# 3_Peripherals.net
KiCad netlist of a schematic drawn in Altium Designer
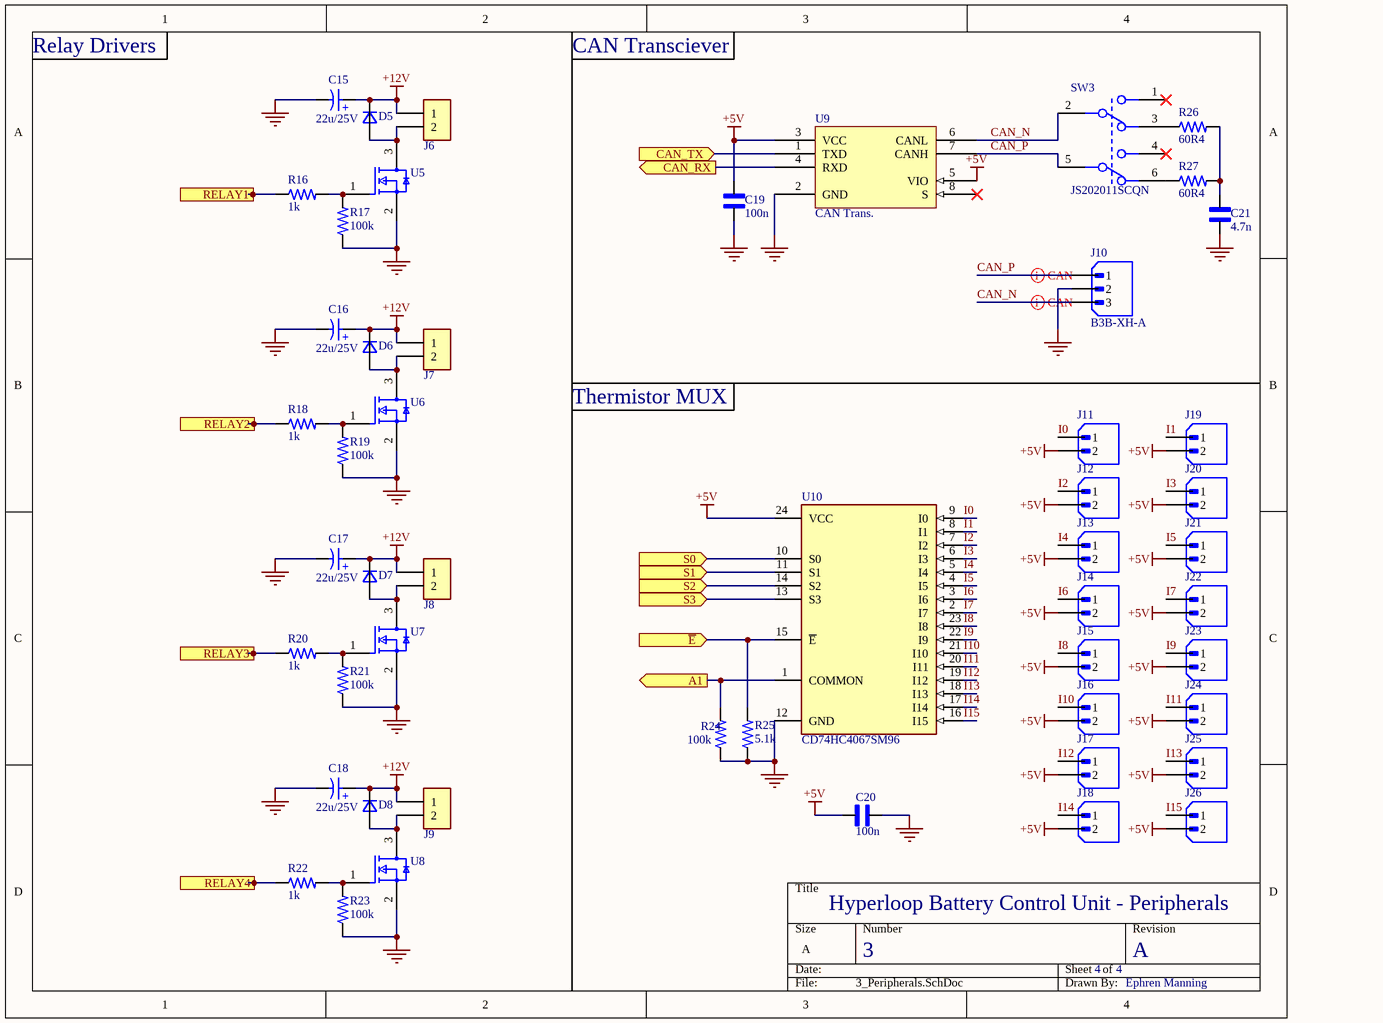
[diagram p0: 3_Peripherals.SchDoc]

(export (version "E")
  (design (tool "Eeschema 10.0.6"))
  (components
    (comp (ref "C15")
      (value "22u/25V")
      (footprint "WCAP-ASLI_D5H5.5")
      (description "22uF/25V Alum")
      (libsource (lib "SAE @ UIC Formula Electric") (part "Capacitor_Polarized"))
    )
    (comp (ref "C16")
      (value "22u/25V")
      (footprint "WCAP-ASLI_D5H5.5")
      (description "22uF/25V Alum")
      (libsource (lib "SAE @ UIC Formula Electric") (part "Capacitor_Polarized"))
    )
    (comp (ref "C17")
      (value "22u/25V")
      (footprint "WCAP-ASLI_D5H5.5")
      (description "22uF/25V Alum")
      (libsource (lib "SAE @ UIC Formula Electric") (part "Capacitor_Polarized"))
    )
    (comp (ref "C18")
      (value "22u/25V")
      (footprint "WCAP-ASLI_D5H5.5")
      (description "22uF/25V Alum")
      (libsource (lib "SAE @ UIC Formula Electric") (part "Capacitor_Polarized"))
    )
    (comp (ref "C19")
      (value "100n")
      (footprint "CAP_0603-Footprint")
      (description "100nF/16V ±10% Ceramic 0603")
      (libsource (lib "SAE @ UIC Formula Electric") (part "CAP_0603-Symbol"))
    )
    (comp (ref "C20")
      (value "100n")
      (footprint "CAP_0603-Footprint")
      (description "100nF/16V ±10% Ceramic 0603")
      (libsource (lib "") (part "CAP_0603-Symbol_1"))
    )
    (comp (ref "C21")
      (value "4.7n")
      (footprint "CAP_0603-Footprint")
      (description "4.7nF/16V 0603 Ceramic Cap")
      (libsource (lib "SAE @ UIC Formula Electric") (part "CAP_0603-Symbol"))
    )
    (comp (ref "D5")
      (value "1N4007FL")
      (footprint "SOD-123_ONS")
      (description "1000V 1A Diode")
      (libsource (lib "SAE @ UIC Formula Electric") (part "1N4007FL-Symbol"))
    )
    (comp (ref "D6")
      (value "1N4007FL")
      (footprint "SOD-123_ONS")
      (description "1000V 1A Diode")
      (libsource (lib "SAE @ UIC Formula Electric") (part "1N4007FL-Symbol"))
    )
    (comp (ref "D7")
      (value "1N4007FL")
      (footprint "SOD-123_ONS")
      (description "1000V 1A Diode")
      (libsource (lib "SAE @ UIC Formula Electric") (part "1N4007FL-Symbol"))
    )
    (comp (ref "D8")
      (value "1N4007FL")
      (footprint "SOD-123_ONS")
      (description "1000V 1A Diode")
      (libsource (lib "SAE @ UIC Formula Electric") (part "1N4007FL-Symbol"))
    )
    (comp (ref "J6")
      (value "282837-2")
      (footprint "TE_282837-2")
      (description "2x Screw Terminal")
      (libsource (lib "SAE @ UIC Formula Electric") (part "282837-2"))
    )
    (comp (ref "J7")
      (value "282837-2")
      (footprint "TE_282837-2")
      (description "2x Screw Terminal")
      (libsource (lib "SAE @ UIC Formula Electric") (part "282837-2"))
    )
    (comp (ref "J8")
      (value "282837-2")
      (footprint "TE_282837-2")
      (description "2x Screw Terminal")
      (libsource (lib "SAE @ UIC Formula Electric") (part "282837-2"))
    )
    (comp (ref "J9")
      (value "282837-2")
      (footprint "TE_282837-2")
      (description "2x Screw Terminal")
      (libsource (lib "SAE @ UIC Formula Electric") (part "282837-2"))
    )
    (comp (ref "J10")
      (value "B3B-XH-A")
      (footprint "JST_B3B-XH-A")
      (description "3x Pin JST-XH-A")
      (libsource (lib "SAE @ UIC Formula Electric") (part "B3B-XH-A"))
    )
    (comp (ref "J11")
      (value "B2B-XH-A")
      (footprint "JST_B2B-XH-A")
      (description "2x Pin JST-XH")
      (libsource (lib "SAE @ UIC Formula Electric") (part "B2B-XH-A"))
    )
    (comp (ref "J12")
      (value "B2B-XH-A")
      (footprint "JST_B2B-XH-A")
      (description "2x Pin JST-XH")
      (libsource (lib "SAE @ UIC Formula Electric") (part "B2B-XH-A"))
    )
    (comp (ref "J13")
      (value "B2B-XH-A")
      (footprint "JST_B2B-XH-A")
      (description "2x Pin JST-XH")
      (libsource (lib "SAE @ UIC Formula Electric") (part "B2B-XH-A"))
    )
    (comp (ref "J14")
      (value "B2B-XH-A")
      (footprint "JST_B2B-XH-A")
      (description "2x Pin JST-XH")
      (libsource (lib "SAE @ UIC Formula Electric") (part "B2B-XH-A"))
    )
    (comp (ref "J15")
      (value "B2B-XH-A")
      (footprint "JST_B2B-XH-A")
      (description "2x Pin JST-XH")
      (libsource (lib "SAE @ UIC Formula Electric") (part "B2B-XH-A"))
    )
    (comp (ref "J16")
      (value "B2B-XH-A")
      (footprint "JST_B2B-XH-A")
      (description "2x Pin JST-XH")
      (libsource (lib "SAE @ UIC Formula Electric") (part "B2B-XH-A"))
    )
    (comp (ref "J17")
      (value "B2B-XH-A")
      (footprint "JST_B2B-XH-A")
      (description "2x Pin JST-XH")
      (libsource (lib "SAE @ UIC Formula Electric") (part "B2B-XH-A"))
    )
    (comp (ref "J18")
      (value "B2B-XH-A")
      (footprint "JST_B2B-XH-A")
      (description "2x Pin JST-XH")
      (libsource (lib "SAE @ UIC Formula Electric") (part "B2B-XH-A"))
    )
    (comp (ref "J19")
      (value "B2B-XH-A")
      (footprint "JST_B2B-XH-A")
      (description "2x Pin JST-XH")
      (libsource (lib "SAE @ UIC Formula Electric") (part "B2B-XH-A"))
    )
    (comp (ref "J20")
      (value "B2B-XH-A")
      (footprint "JST_B2B-XH-A")
      (description "2x Pin JST-XH")
      (libsource (lib "SAE @ UIC Formula Electric") (part "B2B-XH-A"))
    )
    (comp (ref "J21")
      (value "B2B-XH-A")
      (footprint "JST_B2B-XH-A")
      (description "2x Pin JST-XH")
      (libsource (lib "SAE @ UIC Formula Electric") (part "B2B-XH-A"))
    )
    (comp (ref "J22")
      (value "B2B-XH-A")
      (footprint "JST_B2B-XH-A")
      (description "2x Pin JST-XH")
      (libsource (lib "SAE @ UIC Formula Electric") (part "B2B-XH-A"))
    )
    (comp (ref "J23")
      (value "B2B-XH-A")
      (footprint "JST_B2B-XH-A")
      (description "2x Pin JST-XH")
      (libsource (lib "SAE @ UIC Formula Electric") (part "B2B-XH-A"))
    )
    (comp (ref "J24")
      (value "B2B-XH-A")
      (footprint "JST_B2B-XH-A")
      (description "2x Pin JST-XH")
      (libsource (lib "SAE @ UIC Formula Electric") (part "B2B-XH-A"))
    )
    (comp (ref "J25")
      (value "B2B-XH-A")
      (footprint "JST_B2B-XH-A")
      (description "2x Pin JST-XH")
      (libsource (lib "SAE @ UIC Formula Electric") (part "B2B-XH-A"))
    )
    (comp (ref "J26")
      (value "B2B-XH-A")
      (footprint "JST_B2B-XH-A")
      (description "2x Pin JST-XH")
      (libsource (lib "SAE @ UIC Formula Electric") (part "B2B-XH-A"))
    )
    (comp (ref "R16")
      (value "1k")
      (footprint "RES_0603-Footprint-1")
      (description "1k 1% 0.1W 0603")
      (libsource (lib "SAE @ UIC Formula Electric") (part "0603_Res"))
    )
    (comp (ref "R17")
      (value "100k")
      (footprint "RES_0603-Footprint-1")
      (description "100k ±1% 0.1W, 0603")
      (libsource (lib "SAE @ UIC Formula Electric") (part "0603_Res"))
    )
    (comp (ref "R18")
      (value "1k")
      (footprint "RES_0603-Footprint-1")
      (description "1k 1% 0.1W 0603")
      (libsource (lib "SAE @ UIC Formula Electric") (part "0603_Res"))
    )
    (comp (ref "R19")
      (value "100k")
      (footprint "RES_0603-Footprint-1")
      (description "100k ±1% 0.1W, 0603")
      (libsource (lib "SAE @ UIC Formula Electric") (part "0603_Res"))
    )
    (comp (ref "R20")
      (value "1k")
      (footprint "RES_0603-Footprint-1")
      (description "1k 1% 0.1W 0603")
      (libsource (lib "SAE @ UIC Formula Electric") (part "0603_Res"))
    )
    (comp (ref "R21")
      (value "100k")
      (footprint "RES_0603-Footprint-1")
      (description "100k ±1% 0.1W, 0603")
      (libsource (lib "SAE @ UIC Formula Electric") (part "0603_Res"))
    )
    (comp (ref "R22")
      (value "1k")
      (footprint "RES_0603-Footprint-1")
      (description "1k 1% 0.1W 0603")
      (libsource (lib "SAE @ UIC Formula Electric") (part "0603_Res"))
    )
    (comp (ref "R23")
      (value "100k")
      (footprint "RES_0603-Footprint-1")
      (description "100k ±1% 0.1W, 0603")
      (libsource (lib "SAE @ UIC Formula Electric") (part "0603_Res"))
    )
    (comp (ref "R24")
      (value "100k")
      (footprint "RES_0603-Footprint-1")
      (description "100k ±1% 0.1W, 0603")
      (libsource (lib "SAE @ UIC Formula Electric") (part "0603_Res"))
    )
    (comp (ref "R25")
      (value "5.1k")
      (footprint "RES_0603-Footprint-1")
      (description "5.1k Ohms ±1% 0.1W 0603")
      (libsource (lib "SAE @ UIC Formula Electric") (part "0603_Res"))
    )
    (comp (ref "R26")
      (value "60R4")
      (footprint "RES_0603-Footprint-1")
      (description "60.4 Ohms ±1% 0.1W 0603")
      (libsource (lib "SAE @ UIC Formula Electric") (part "0603_Res"))
    )
    (comp (ref "R27")
      (value "60R4")
      (footprint "RES_0603-Footprint-1")
      (description "60.4 Ohms ±1% 0.1W 0603")
      (libsource (lib "SAE @ UIC Formula Electric") (part "0603_Res"))
    )
    (comp (ref "SW3")
      (value "JS202011SCQN")
      (footprint "FP-JS202011SCQN-MFG")
      (description "DPDT SMD SWITCH 300mA 6V")
      (libsource (lib "SAE @ UIC Formula Electric") (part "ac99ea1af431c19115f5225061c5c88"))
    )
    (comp (ref "U5")
      (value "PMV20XNER")
      (footprint "SOT95P230X110-3N")
      (description "N-Channel 30 V 5.7A (Ta) 510mW (Ta), 6.94W (Tc) Surface Mount TO-236AB")
      (libsource (lib "SAE @ UIC Formula Electric") (part "PMV20XNER"))
    )
    (comp (ref "U6")
      (value "PMV20XNER")
      (footprint "SOT95P230X110-3N")
      (description "N-Channel 30 V 5.7A (Ta) 510mW (Ta), 6.94W (Tc) Surface Mount TO-236AB")
      (libsource (lib "SAE @ UIC Formula Electric") (part "PMV20XNER"))
    )
    (comp (ref "U7")
      (value "PMV20XNER")
      (footprint "SOT95P230X110-3N")
      (description "N-Channel 30 V 5.7A (Ta) 510mW (Ta), 6.94W (Tc) Surface Mount TO-236AB")
      (libsource (lib "SAE @ UIC Formula Electric") (part "PMV20XNER"))
    )
    (comp (ref "U8")
      (value "PMV20XNER")
      (footprint "SOT95P230X110-3N")
      (description "N-Channel 30 V 5.7A (Ta) 510mW (Ta), 6.94W (Tc) Surface Mount TO-236AB")
      (libsource (lib "SAE @ UIC Formula Electric") (part "PMV20XNER"))
    )
    (comp (ref "U9")
      (value "CAN Trans.")
      (footprint "SOIC127P600X175-8N")
      (description "CAN Transceiver, NXP")
      (libsource (lib "SAE @ UIC Formula Electric") (part "TJA1051T_3, 118-Symbol-1"))
    )
    (comp (ref "U10")
      (value "CD74HC4067SM96")
      (footprint "CD74HC4067SM96 - SSOP24")
      (description "16:1 Mux 160 Ohm 24-SSOP")
      (libsource (lib "SAE @ UIC Formula Electric") (part "CD74HC4067"))
    )
  )
  (nets
    (net (code "1") (name "+5V") (class "Default")
      (node (ref "C19") (pin "2") (pinfunction "2_2") (pintype "passive"))
      (node (ref "C20") (pin "2") (pinfunction "2_2") (pintype "passive"))
      (node (ref "J11") (pin "2") (pinfunction "2_2") (pintype "passive"))
      (node (ref "J12") (pin "2") (pinfunction "2_2") (pintype "passive"))
      (node (ref "J13") (pin "2") (pinfunction "2_2") (pintype "passive"))
      (node (ref "J14") (pin "2") (pinfunction "2_2") (pintype "passive"))
      (node (ref "J15") (pin "2") (pinfunction "2_2") (pintype "passive"))
      (node (ref "J16") (pin "2") (pinfunction "2_2") (pintype "passive"))
      (node (ref "J17") (pin "2") (pinfunction "2_2") (pintype "passive"))
      (node (ref "J18") (pin "2") (pinfunction "2_2") (pintype "passive"))
      (node (ref "J19") (pin "2") (pinfunction "2_2") (pintype "passive"))
      (node (ref "J20") (pin "2") (pinfunction "2_2") (pintype "passive"))
      (node (ref "J21") (pin "2") (pinfunction "2_2") (pintype "passive"))
      (node (ref "J22") (pin "2") (pinfunction "2_2") (pintype "passive"))
      (node (ref "J23") (pin "2") (pinfunction "2_2") (pintype "passive"))
      (node (ref "J24") (pin "2") (pinfunction "2_2") (pintype "passive"))
      (node (ref "J25") (pin "2") (pinfunction "2_2") (pintype "passive"))
      (node (ref "J26") (pin "2") (pinfunction "2_2") (pintype "passive"))
      (node (ref "U10") (pin "24") (pinfunction "VCC_24") (pintype "passive"))
      (node (ref "U9") (pin "3") (pinfunction "VCC_3") (pintype "passive"))
      (node (ref "U9") (pin "5") (pinfunction "VIO_5") (pintype "input"))
    )
    (net (code "2") (name "+12V") (class "Default")
      (node (ref "C15") (pin "1") (pinfunction "P_1") (pintype "passive"))
      (node (ref "C16") (pin "1") (pinfunction "P_1") (pintype "passive"))
      (node (ref "C17") (pin "1") (pinfunction "P_1") (pintype "passive"))
      (node (ref "C18") (pin "1") (pinfunction "P_1") (pintype "passive"))
      (node (ref "D5") (pin "1") (pinfunction "K_1") (pintype "passive"))
      (node (ref "D6") (pin "1") (pinfunction "K_1") (pintype "passive"))
      (node (ref "D7") (pin "1") (pinfunction "K_1") (pintype "passive"))
      (node (ref "D8") (pin "1") (pinfunction "K_1") (pintype "passive"))
      (node (ref "J6") (pin "1") (pinfunction "1_1") (pintype "passive"))
      (node (ref "J7") (pin "1") (pinfunction "1_1") (pintype "passive"))
      (node (ref "J8") (pin "1") (pinfunction "1_1") (pintype "passive"))
      (node (ref "J9") (pin "1") (pinfunction "1_1") (pintype "passive"))
    )
    (net (code "3") (name "/A1") (class "Default")
      (node (ref "R24") (pin "2") (pinfunction "2_2") (pintype "passive"))
      (node (ref "U10") (pin "1") (pinfunction "COMMON_1") (pintype "passive"))
    )
    (net (code "4") (name "/CAN_N") (class "Default")
      (node (ref "J10") (pin "3") (pinfunction "3_3") (pintype "passive"))
      (node (ref "SW3") (pin "2") (pinfunction "2_2") (pintype "passive"))
      (node (ref "U9") (pin "6") (pinfunction "CANL_6") (pintype "passive"))
    )
    (net (code "5") (name "/CAN_P") (class "Default")
      (node (ref "J10") (pin "1") (pinfunction "1_1") (pintype "passive"))
      (node (ref "SW3") (pin "5") (pinfunction "5_5") (pintype "passive"))
      (node (ref "U9") (pin "7") (pinfunction "CANH_7") (pintype "passive"))
    )
    (net (code "6") (name "/CAN_RX") (class "Default")
      (node (ref "U9") (pin "4") (pinfunction "RXD_4") (pintype "passive"))
    )
    (net (code "7") (name "/CAN_TX") (class "Default")
      (node (ref "U9") (pin "1") (pinfunction "TXD_1") (pintype "passive"))
    )
    (net (code "8") (name "/I0") (class "Default")
      (node (ref "J11") (pin "1") (pinfunction "1_1") (pintype "passive"))
      (node (ref "U10") (pin "9") (pinfunction "I0_9") (pintype "input"))
    )
    (net (code "9") (name "/I1") (class "Default")
      (node (ref "J19") (pin "1") (pinfunction "1_1") (pintype "passive"))
      (node (ref "U10") (pin "8") (pinfunction "I1_8") (pintype "input"))
    )
    (net (code "10") (name "/I2") (class "Default")
      (node (ref "J12") (pin "1") (pinfunction "1_1") (pintype "passive"))
      (node (ref "U10") (pin "7") (pinfunction "I2_7") (pintype "input"))
    )
    (net (code "11") (name "/I3") (class "Default")
      (node (ref "J20") (pin "1") (pinfunction "1_1") (pintype "passive"))
      (node (ref "U10") (pin "6") (pinfunction "I3_6") (pintype "input"))
    )
    (net (code "12") (name "/I4") (class "Default")
      (node (ref "J13") (pin "1") (pinfunction "1_1") (pintype "passive"))
      (node (ref "U10") (pin "5") (pinfunction "I4_5") (pintype "input"))
    )
    (net (code "13") (name "/I5") (class "Default")
      (node (ref "J21") (pin "1") (pinfunction "1_1") (pintype "passive"))
      (node (ref "U10") (pin "4") (pinfunction "I5_4") (pintype "input"))
    )
    (net (code "14") (name "/I6") (class "Default")
      (node (ref "J14") (pin "1") (pinfunction "1_1") (pintype "passive"))
      (node (ref "U10") (pin "3") (pinfunction "I6_3") (pintype "input"))
    )
    (net (code "15") (name "/I7") (class "Default")
      (node (ref "J22") (pin "1") (pinfunction "1_1") (pintype "passive"))
      (node (ref "U10") (pin "2") (pinfunction "I7_2") (pintype "input"))
    )
    (net (code "16") (name "/I8") (class "Default")
      (node (ref "J15") (pin "1") (pinfunction "1_1") (pintype "passive"))
      (node (ref "U10") (pin "23") (pinfunction "I8_23") (pintype "input"))
    )
    (net (code "17") (name "/I9") (class "Default")
      (node (ref "J23") (pin "1") (pinfunction "1_1") (pintype "passive"))
      (node (ref "U10") (pin "22") (pinfunction "I9_22") (pintype "input"))
    )
    (net (code "18") (name "/I10") (class "Default")
      (node (ref "J16") (pin "1") (pinfunction "1_1") (pintype "passive"))
      (node (ref "U10") (pin "21") (pinfunction "I10_21") (pintype "input"))
    )
    (net (code "19") (name "/I11") (class "Default")
      (node (ref "J24") (pin "1") (pinfunction "1_1") (pintype "passive"))
      (node (ref "U10") (pin "20") (pinfunction "I11_20") (pintype "input"))
    )
    (net (code "20") (name "/I12") (class "Default")
      (node (ref "J17") (pin "1") (pinfunction "1_1") (pintype "passive"))
      (node (ref "U10") (pin "19") (pinfunction "I12_19") (pintype "input"))
    )
    (net (code "21") (name "/I13") (class "Default")
      (node (ref "J25") (pin "1") (pinfunction "1_1") (pintype "passive"))
      (node (ref "U10") (pin "18") (pinfunction "I13_18") (pintype "input"))
    )
    (net (code "22") (name "/I14") (class "Default")
      (node (ref "J18") (pin "1") (pinfunction "1_1") (pintype "passive"))
      (node (ref "U10") (pin "17") (pinfunction "I14_17") (pintype "input"))
    )
    (net (code "23") (name "/I15") (class "Default")
      (node (ref "J26") (pin "1") (pinfunction "1_1") (pintype "passive"))
      (node (ref "U10") (pin "16") (pinfunction "I15_16") (pintype "input"))
    )
    (net (code "24") (name "/RELAY1") (class "Default")
      (node (ref "R16") (pin "1") (pinfunction "1_1") (pintype "passive"))
    )
    (net (code "25") (name "/RELAY2") (class "Default")
      (node (ref "R18") (pin "1") (pinfunction "1_1") (pintype "passive"))
    )
    (net (code "26") (name "/RELAY3") (class "Default")
      (node (ref "R20") (pin "1") (pinfunction "1_1") (pintype "passive"))
    )
    (net (code "27") (name "/RELAY4") (class "Default")
      (node (ref "R22") (pin "1") (pinfunction "1_1") (pintype "passive"))
    )
    (net (code "28") (name "/S0") (class "Default")
      (node (ref "U10") (pin "10") (pinfunction "S0_10") (pintype "passive"))
    )
    (net (code "29") (name "/S1") (class "Default")
      (node (ref "U10") (pin "11") (pinfunction "S1_11") (pintype "passive"))
    )
    (net (code "30") (name "/S2") (class "Default")
      (node (ref "U10") (pin "14") (pinfunction "S2_14") (pintype "passive"))
    )
    (net (code "31") (name "/S3") (class "Default")
      (node (ref "U10") (pin "13") (pinfunction "S3_13") (pintype "passive"))
    )
    (net (code "32") (name "/~{E}") (class "Default")
      (node (ref "R25") (pin "2") (pinfunction "2_2") (pintype "passive"))
      (node (ref "U10") (pin "15") (pinfunction "~{E}_15") (pintype "passive"))
    )
    (net (code "33") (name "GND") (class "Default")
      (node (ref "C15") (pin "2") (pinfunction "N_2") (pintype "passive"))
      (node (ref "C16") (pin "2") (pinfunction "N_2") (pintype "passive"))
      (node (ref "C17") (pin "2") (pinfunction "N_2") (pintype "passive"))
      (node (ref "C18") (pin "2") (pinfunction "N_2") (pintype "passive"))
      (node (ref "C19") (pin "1") (pinfunction "1_1") (pintype "passive"))
      (node (ref "C20") (pin "1") (pinfunction "1_1") (pintype "passive"))
      (node (ref "C21") (pin "1") (pinfunction "1_1") (pintype "passive"))
      (node (ref "J10") (pin "2") (pinfunction "2_2") (pintype "passive"))
      (node (ref "R17") (pin "1") (pinfunction "1_1") (pintype "passive"))
      (node (ref "R19") (pin "1") (pinfunction "1_1") (pintype "passive"))
      (node (ref "R21") (pin "1") (pinfunction "1_1") (pintype "passive"))
      (node (ref "R23") (pin "1") (pinfunction "1_1") (pintype "passive"))
      (node (ref "R24") (pin "1") (pinfunction "1_1") (pintype "passive"))
      (node (ref "R25") (pin "1") (pinfunction "1_1") (pintype "passive"))
      (node (ref "U10") (pin "12") (pinfunction "GND_12") (pintype "power_in"))
      (node (ref "U5") (pin "2") (pinfunction "Source_2") (pintype "passive"))
      (node (ref "U6") (pin "2") (pinfunction "Source_2") (pintype "passive"))
      (node (ref "U7") (pin "2") (pinfunction "Source_2") (pintype "passive"))
      (node (ref "U8") (pin "2") (pinfunction "Source_2") (pintype "passive"))
      (node (ref "U9") (pin "2") (pinfunction "GND_2") (pintype "passive"))
    )
    (net (code "34") (name "Net-(C21-Pad2)") (class "Default")
      (node (ref "C21") (pin "2") (pinfunction "2_2") (pintype "passive"))
      (node (ref "R26") (pin "2") (pinfunction "2_2") (pintype "passive"))
      (node (ref "R27") (pin "2") (pinfunction "2_2") (pintype "passive"))
    )
    (net (code "35") (name "Net-(D5-A)") (class "Default")
      (node (ref "D5") (pin "2") (pinfunction "A_2") (pintype "passive"))
      (node (ref "J6") (pin "2") (pinfunction "2_2") (pintype "passive"))
      (node (ref "U5") (pin "3") (pinfunction "Drain_3") (pintype "passive"))
    )
    (net (code "36") (name "Net-(D6-A)") (class "Default")
      (node (ref "D6") (pin "2") (pinfunction "A_2") (pintype "passive"))
      (node (ref "J7") (pin "2") (pinfunction "2_2") (pintype "passive"))
      (node (ref "U6") (pin "3") (pinfunction "Drain_3") (pintype "passive"))
    )
    (net (code "37") (name "Net-(D7-A)") (class "Default")
      (node (ref "D7") (pin "2") (pinfunction "A_2") (pintype "passive"))
      (node (ref "J8") (pin "2") (pinfunction "2_2") (pintype "passive"))
      (node (ref "U7") (pin "3") (pinfunction "Drain_3") (pintype "passive"))
    )
    (net (code "38") (name "Net-(D8-A)") (class "Default")
      (node (ref "D8") (pin "2") (pinfunction "A_2") (pintype "passive"))
      (node (ref "J9") (pin "2") (pinfunction "2_2") (pintype "passive"))
      (node (ref "U8") (pin "3") (pinfunction "Drain_3") (pintype "passive"))
    )
    (net (code "39") (name "Net-(R26-Pad1)") (class "Default")
      (node (ref "R26") (pin "1") (pinfunction "1_1") (pintype "passive"))
      (node (ref "SW3") (pin "3") (pinfunction "3_3") (pintype "passive"))
    )
    (net (code "40") (name "Net-(R27-Pad1)") (class "Default")
      (node (ref "R27") (pin "1") (pinfunction "1_1") (pintype "passive"))
      (node (ref "SW3") (pin "6") (pinfunction "6_6") (pintype "passive"))
    )
    (net (code "41") (name "Net-(U5-Gate)") (class "Default")
      (node (ref "R16") (pin "2") (pinfunction "2_2") (pintype "passive"))
      (node (ref "R17") (pin "2") (pinfunction "2_2") (pintype "passive"))
      (node (ref "U5") (pin "1") (pinfunction "Gate_1") (pintype "passive"))
    )
    (net (code "42") (name "Net-(U6-Gate)") (class "Default")
      (node (ref "R18") (pin "2") (pinfunction "2_2") (pintype "passive"))
      (node (ref "R19") (pin "2") (pinfunction "2_2") (pintype "passive"))
      (node (ref "U6") (pin "1") (pinfunction "Gate_1") (pintype "passive"))
    )
    (net (code "43") (name "Net-(U7-Gate)") (class "Default")
      (node (ref "R20") (pin "2") (pinfunction "2_2") (pintype "passive"))
      (node (ref "R21") (pin "2") (pinfunction "2_2") (pintype "passive"))
      (node (ref "U7") (pin "1") (pinfunction "Gate_1") (pintype "passive"))
    )
    (net (code "44") (name "Net-(U8-Gate)") (class "Default")
      (node (ref "R22") (pin "2") (pinfunction "2_2") (pintype "passive"))
      (node (ref "R23") (pin "2") (pinfunction "2_2") (pintype "passive"))
      (node (ref "U8") (pin "1") (pinfunction "Gate_1") (pintype "passive"))
    )
    (net (code "45") (name "unconnected-(SW3-Pad1)") (class "Default")
      (node (ref "SW3") (pin "1") (pinfunction "1_1") (pintype "passive+no_connect"))
    )
    (net (code "46") (name "unconnected-(SW3-Pad4)") (class "Default")
      (node (ref "SW3") (pin "4") (pinfunction "4_4") (pintype "passive+no_connect"))
    )
    (net (code "47") (name "unconnected-(U9-S-Pad8)") (class "Default")
      (node (ref "U9") (pin "8") (pinfunction "S_8") (pintype "input+no_connect"))
    )
  )
)
